# SparkFun_Magnetometer_MMC5983MA_Qwiic_Mi.net
KiCad netlist of a schematic drawn in EAGLE
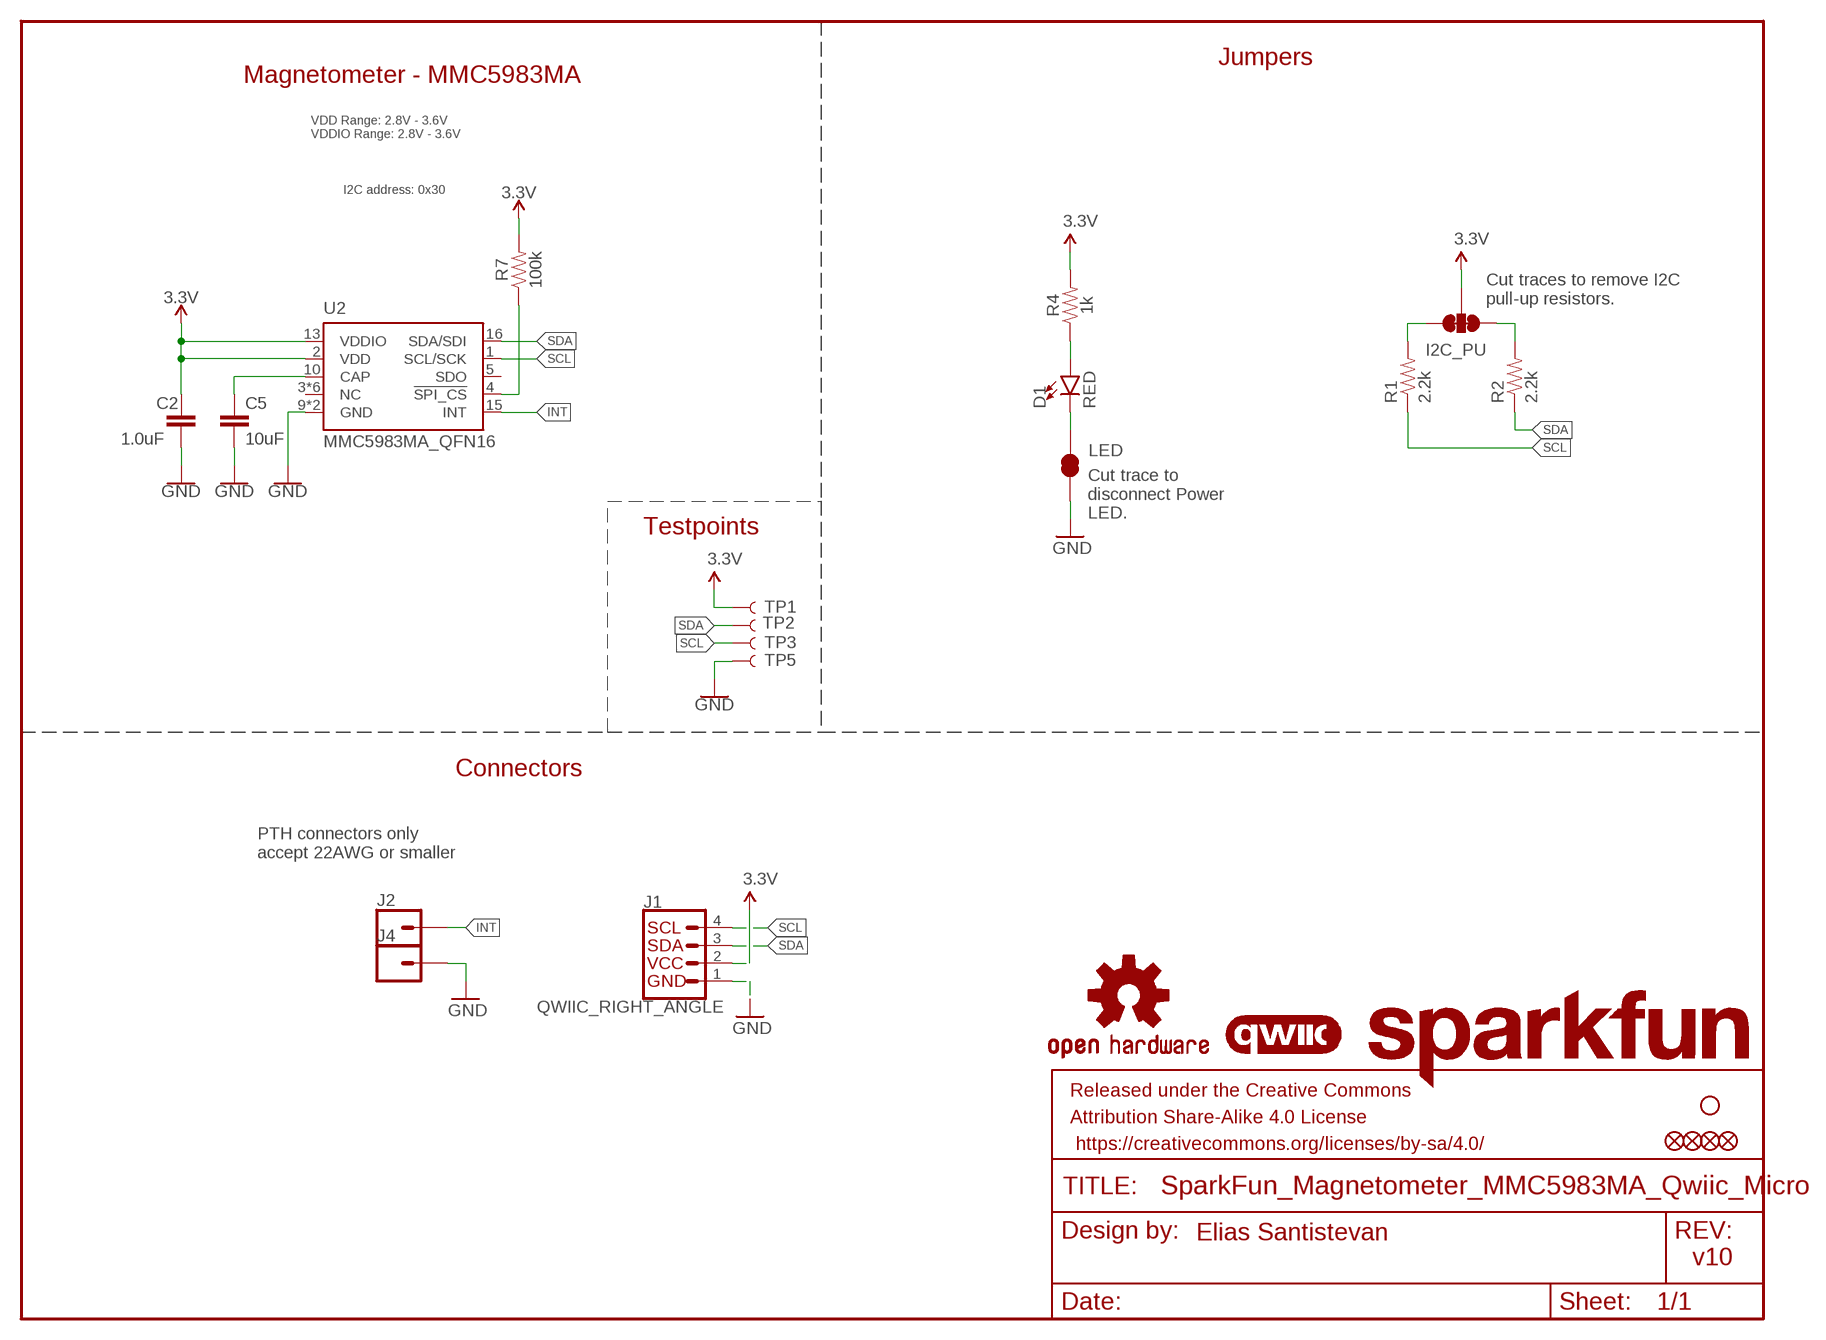
[diagram p0: schematic, sheet 1]

(export (version "E")
  (design (tool "Eeschema 10.0.6"))
  (components
    (comp (ref "C2")
      (value "1.0uF")
      (footprint "eagle-import:0402-TIGHT")
      (libsource (lib "eagle-import") (part "1.0UF-0402T-16V-10%"))
    )
    (comp (ref "C5")
      (value "10uF")
      (footprint "eagle-import:0402-TIGHT")
      (libsource (lib "eagle-import") (part "10UF-0402T-6.3V-20%"))
    )
    (comp (ref "D1")
      (value "RED")
      (footprint "eagle-import:LED-0402")
      (libsource (lib "eagle-import") (part "LED-RED_0402"))
    )
    (comp (ref "FD1")
      (value "FIDUCIALUFIDUCIAL")
      (footprint "eagle-import:FIDUCIAL-MICRO")
      (libsource (lib "eagle-import") (part "FIDUCIALUFIDUCIAL"))
    )
    (comp (ref "FD2")
      (value "FIDUCIALUFIDUCIAL")
      (footprint "eagle-import:FIDUCIAL-MICRO")
      (libsource (lib "eagle-import") (part "FIDUCIALUFIDUCIAL"))
    )
    (comp (ref "FID1")
      (value "FIDUCIALUFIDUCIAL")
      (footprint "eagle-import:FIDUCIAL-MICRO")
      (libsource (lib "eagle-import") (part "FIDUCIALUFIDUCIAL"))
    )
    (comp (ref "FID2")
      (value "FIDUCIALUFIDUCIAL")
      (footprint "eagle-import:FIDUCIAL-MICRO")
      (libsource (lib "eagle-import") (part "FIDUCIALUFIDUCIAL"))
    )
    (comp (ref "FRAME1")
      (value "FRAME-LETTER")
      (footprint "eagle-import:CREATIVE_COMMONS")
      (fields (field (name "DESIGNER") "Elias Santistevan"))
      (libsource (lib "eagle-import") (part "FRAME-LETTER"))
    )
    (comp (ref "I2C_PU")
      (value "S_MODE")
      (footprint "eagle-import:SMT-JUMPER_3_2-NC_TRACE_SILK")
      (libsource (lib "eagle-import") (part "JUMPER-SMT_3_2-NC_TRACE_SILK"))
    )
    (comp (ref "J1")
      (value "QWIIC_RIGHT_ANGLE")
      (footprint "eagle-import:JST04_1MM_RA")
      (libsource (lib "eagle-import") (part "QWIIC_CONNECTORJS-1MM"))
    )
    (comp (ref "J2")
      (value "CONN_01_1MM")
      (footprint "eagle-import:1X01_1MM_NO_SILK")
      (libsource (lib "eagle-import") (part "CONN_01_1MM"))
    )
    (comp (ref "J4")
      (value "CONN_01_1MM")
      (footprint "eagle-import:1X01_1MM_NO_SILK")
      (libsource (lib "eagle-import") (part "CONN_01_1MM"))
    )
    (comp (ref "LED")
      (value "JUMPER-SMT_2_NC_TRACE_SILK")
      (footprint "eagle-import:SMT-JUMPER_2_NC_TRACE_SILK")
      (libsource (lib "eagle-import") (part "JUMPER-SMT_2_NC_TRACE_SILK"))
    )
    (comp (ref "LOGO1")
      (value "QWIIC_LOGO_4MM")
      (footprint "eagle-import:QWIIC_4MM")
      (libsource (lib "eagle-import") (part "QWIIC_LOGO_4MM"))
    )
    (comp (ref "LOGO2")
      (value "OSHW-LOGOMINI")
      (footprint "eagle-import:OSHW-LOGO-MINI")
      (libsource (lib "eagle-import") (part "OSHW-LOGOMINI"))
    )
    (comp (ref "LOGO3")
      (value "SFE_LOGO_NAMEBLANK")
      (footprint "eagle-import:BLANK")
      (libsource (lib "eagle-import") (part "SFE_LOGO_NAMEBLANK"))
    )
    (comp (ref "R1")
      (value "2.2k")
      (footprint "eagle-import:0402-TIGHT")
      (libsource (lib "eagle-import") (part "2.2KOHM-0402T-1/16W-1%"))
    )
    (comp (ref "R2")
      (value "2.2k")
      (footprint "eagle-import:0402-TIGHT")
      (libsource (lib "eagle-import") (part "2.2KOHM-0402T-1/16W-1%"))
    )
    (comp (ref "R4")
      (value "1k")
      (footprint "eagle-import:0402-TIGHT")
      (libsource (lib "eagle-import") (part "1KOHM-0402T-1/16W-1%"))
    )
    (comp (ref "R7")
      (value "100k")
      (footprint "eagle-import:0402-TIGHT")
      (libsource (lib "eagle-import") (part "100KOHM-0402T-1/16W-1%"))
    )
    (comp (ref "STANDOFF3")
      (value "STAND-OFFTIGHT")
      (footprint "eagle-import:STAND-OFF-TIGHT")
      (libsource (lib "eagle-import") (part "STAND-OFFTIGHT"))
    )
    (comp (ref "TP1")
      (value "TEST-POINT3")
      (footprint "eagle-import:PAD.03X.03")
      (libsource (lib "eagle-import") (part "TEST-POINT3"))
    )
    (comp (ref "TP2")
      (value "TEST-POINT3")
      (footprint "eagle-import:PAD.03X.03")
      (libsource (lib "eagle-import") (part "TEST-POINT3"))
    )
    (comp (ref "TP3")
      (value "TEST-POINT3")
      (footprint "eagle-import:PAD.03X.03")
      (libsource (lib "eagle-import") (part "TEST-POINT3"))
    )
    (comp (ref "TP5")
      (value "TEST-POINT3")
      (footprint "eagle-import:PAD.03X.03")
      (libsource (lib "eagle-import") (part "TEST-POINT3"))
    )
    (comp (ref "U2")
      (value "MMC5983MA_QFN16")
      (footprint "eagle-import:LGA-16-3X3MM-4X4PINS")
      (libsource (lib "eagle-import") (part "MMC5983MA_QFN16"))
    )
  )
  (nets
    (net (code "1") (name "3.3V") (class "Default")
      (node (ref "C2") (pin "1") (pinfunction "1_1") (pintype "passive"))
      (node (ref "I2C_PU") (pin "2") (pinfunction "2_2") (pintype "passive"))
      (node (ref "J1") (pin "2") (pinfunction "2_2") (pintype "power_in"))
      (node (ref "R4") (pin "2") (pinfunction "2_2") (pintype "passive"))
      (node (ref "R7") (pin "2") (pinfunction "2_2") (pintype "passive"))
      (node (ref "TP1") (pin "1") (pinfunction "1_1") (pintype "bidirectional"))
      (node (ref "U2") (pin "13") (pinfunction "VDDIO_13") (pintype "power_in"))
      (node (ref "U2") (pin "2") (pinfunction "VDD_2") (pintype "power_in"))
    )
    (net (code "2") (name "GND") (class "Default")
      (node (ref "C2") (pin "2") (pinfunction "2_2") (pintype "passive"))
      (node (ref "C5") (pin "2") (pinfunction "2_2") (pintype "passive"))
      (node (ref "J1") (pin "1") (pinfunction "1_1") (pintype "power_in"))
      (node (ref "J4") (pin "1") (pinfunction "1_1") (pintype "passive"))
      (node (ref "LED") (pin "1") (pinfunction "1_1") (pintype "passive"))
      (node (ref "TP5") (pin "1") (pinfunction "1_1") (pintype "bidirectional"))
      (node (ref "U2") (pin "11") (pinfunction "GND_11") (pintype "power_in"))
      (node (ref "U2") (pin "9") (pinfunction "GND_9") (pintype "power_in"))
    )
    (net (code "3") (name "INT") (class "Default")
      (node (ref "J2") (pin "1") (pinfunction "1_1") (pintype "passive"))
      (node (ref "U2") (pin "15") (pinfunction "INT_15") (pintype "output"))
    )
    (net (code "4") (name "Net-(D1-PadA)") (class "Default")
      (node (ref "D1") (pin "A") (pinfunction "A_A") (pintype "passive"))
      (node (ref "R4") (pin "1") (pinfunction "1_1") (pintype "passive"))
    )
    (net (code "5") (name "Net-(D1-PadC)") (class "Default")
      (node (ref "D1") (pin "C") (pinfunction "C_C") (pintype "passive"))
      (node (ref "LED") (pin "2") (pinfunction "2_2") (pintype "passive"))
    )
    (net (code "6") (name "Net-(I2C_PU-Pad1)") (class "Default")
      (node (ref "I2C_PU") (pin "1") (pinfunction "1_1") (pintype "passive"))
      (node (ref "R1") (pin "2") (pinfunction "2_2") (pintype "passive"))
    )
    (net (code "7") (name "Net-(I2C_PU-Pad3)") (class "Default")
      (node (ref "I2C_PU") (pin "3") (pinfunction "3_3") (pintype "passive"))
      (node (ref "R2") (pin "2") (pinfunction "2_2") (pintype "passive"))
    )
    (net (code "8") (name "Net-(U2-CAP)") (class "Default")
      (node (ref "C5") (pin "1") (pinfunction "1_1") (pintype "passive"))
      (node (ref "U2") (pin "10") (pinfunction "CAP_10") (pintype "passive"))
    )
    (net (code "9") (name "Net-(U2-~{SPI_CS})") (class "Default")
      (node (ref "R7") (pin "1") (pinfunction "1_1") (pintype "passive"))
      (node (ref "U2") (pin "4") (pinfunction "~{SPI_CS}_4") (pintype "input"))
    )
    (net (code "10") (name "SCL") (class "Default")
      (node (ref "J1") (pin "4") (pinfunction "4_4") (pintype "passive"))
      (node (ref "R1") (pin "1") (pinfunction "1_1") (pintype "passive"))
      (node (ref "TP3") (pin "1") (pinfunction "1_1") (pintype "bidirectional"))
      (node (ref "U2") (pin "1") (pinfunction "SCL/SCK_1") (pintype "bidirectional"))
    )
    (net (code "11") (name "SDA") (class "Default")
      (node (ref "J1") (pin "3") (pinfunction "3_3") (pintype "passive"))
      (node (ref "R2") (pin "1") (pinfunction "1_1") (pintype "passive"))
      (node (ref "TP2") (pin "1") (pinfunction "1_1") (pintype "bidirectional"))
      (node (ref "U2") (pin "16") (pinfunction "SDA/SDI_16") (pintype "bidirectional"))
    )
    (net (code "12") (name "unconnected-(U2-NC-Pad3)") (class "Default")
      (node (ref "U2") (pin "3") (pinfunction "NC_3") (pintype "no_connect"))
    )
    (net (code "13") (name "unconnected-(U2-NC-Pad6)") (class "Default")
      (node (ref "U2") (pin "6") (pinfunction "NC_6") (pintype "no_connect"))
    )
    (net (code "14") (name "unconnected-(U2-NC-Pad7)") (class "Default")
      (node (ref "U2") (pin "7") (pinfunction "NC_7") (pintype "no_connect"))
    )
    (net (code "15") (name "unconnected-(U2-NC-Pad8)") (class "Default")
      (node (ref "U2") (pin "8") (pinfunction "NC_8") (pintype "no_connect"))
    )
    (net (code "16") (name "unconnected-(U2-NC-Pad12)") (class "Default")
      (node (ref "U2") (pin "12") (pinfunction "NC_12") (pintype "no_connect"))
    )
    (net (code "17") (name "unconnected-(U2-NC-Pad14)") (class "Default")
      (node (ref "U2") (pin "14") (pinfunction "NC_14") (pintype "no_connect"))
    )
    (net (code "18") (name "unconnected-(U2-SDO-Pad5)") (class "Default")
      (node (ref "U2") (pin "5") (pinfunction "SDO_5") (pintype "output"))
    )
  )
)
